# project-tsc.net
KiCad netlist of a schematic drawn in EAGLE
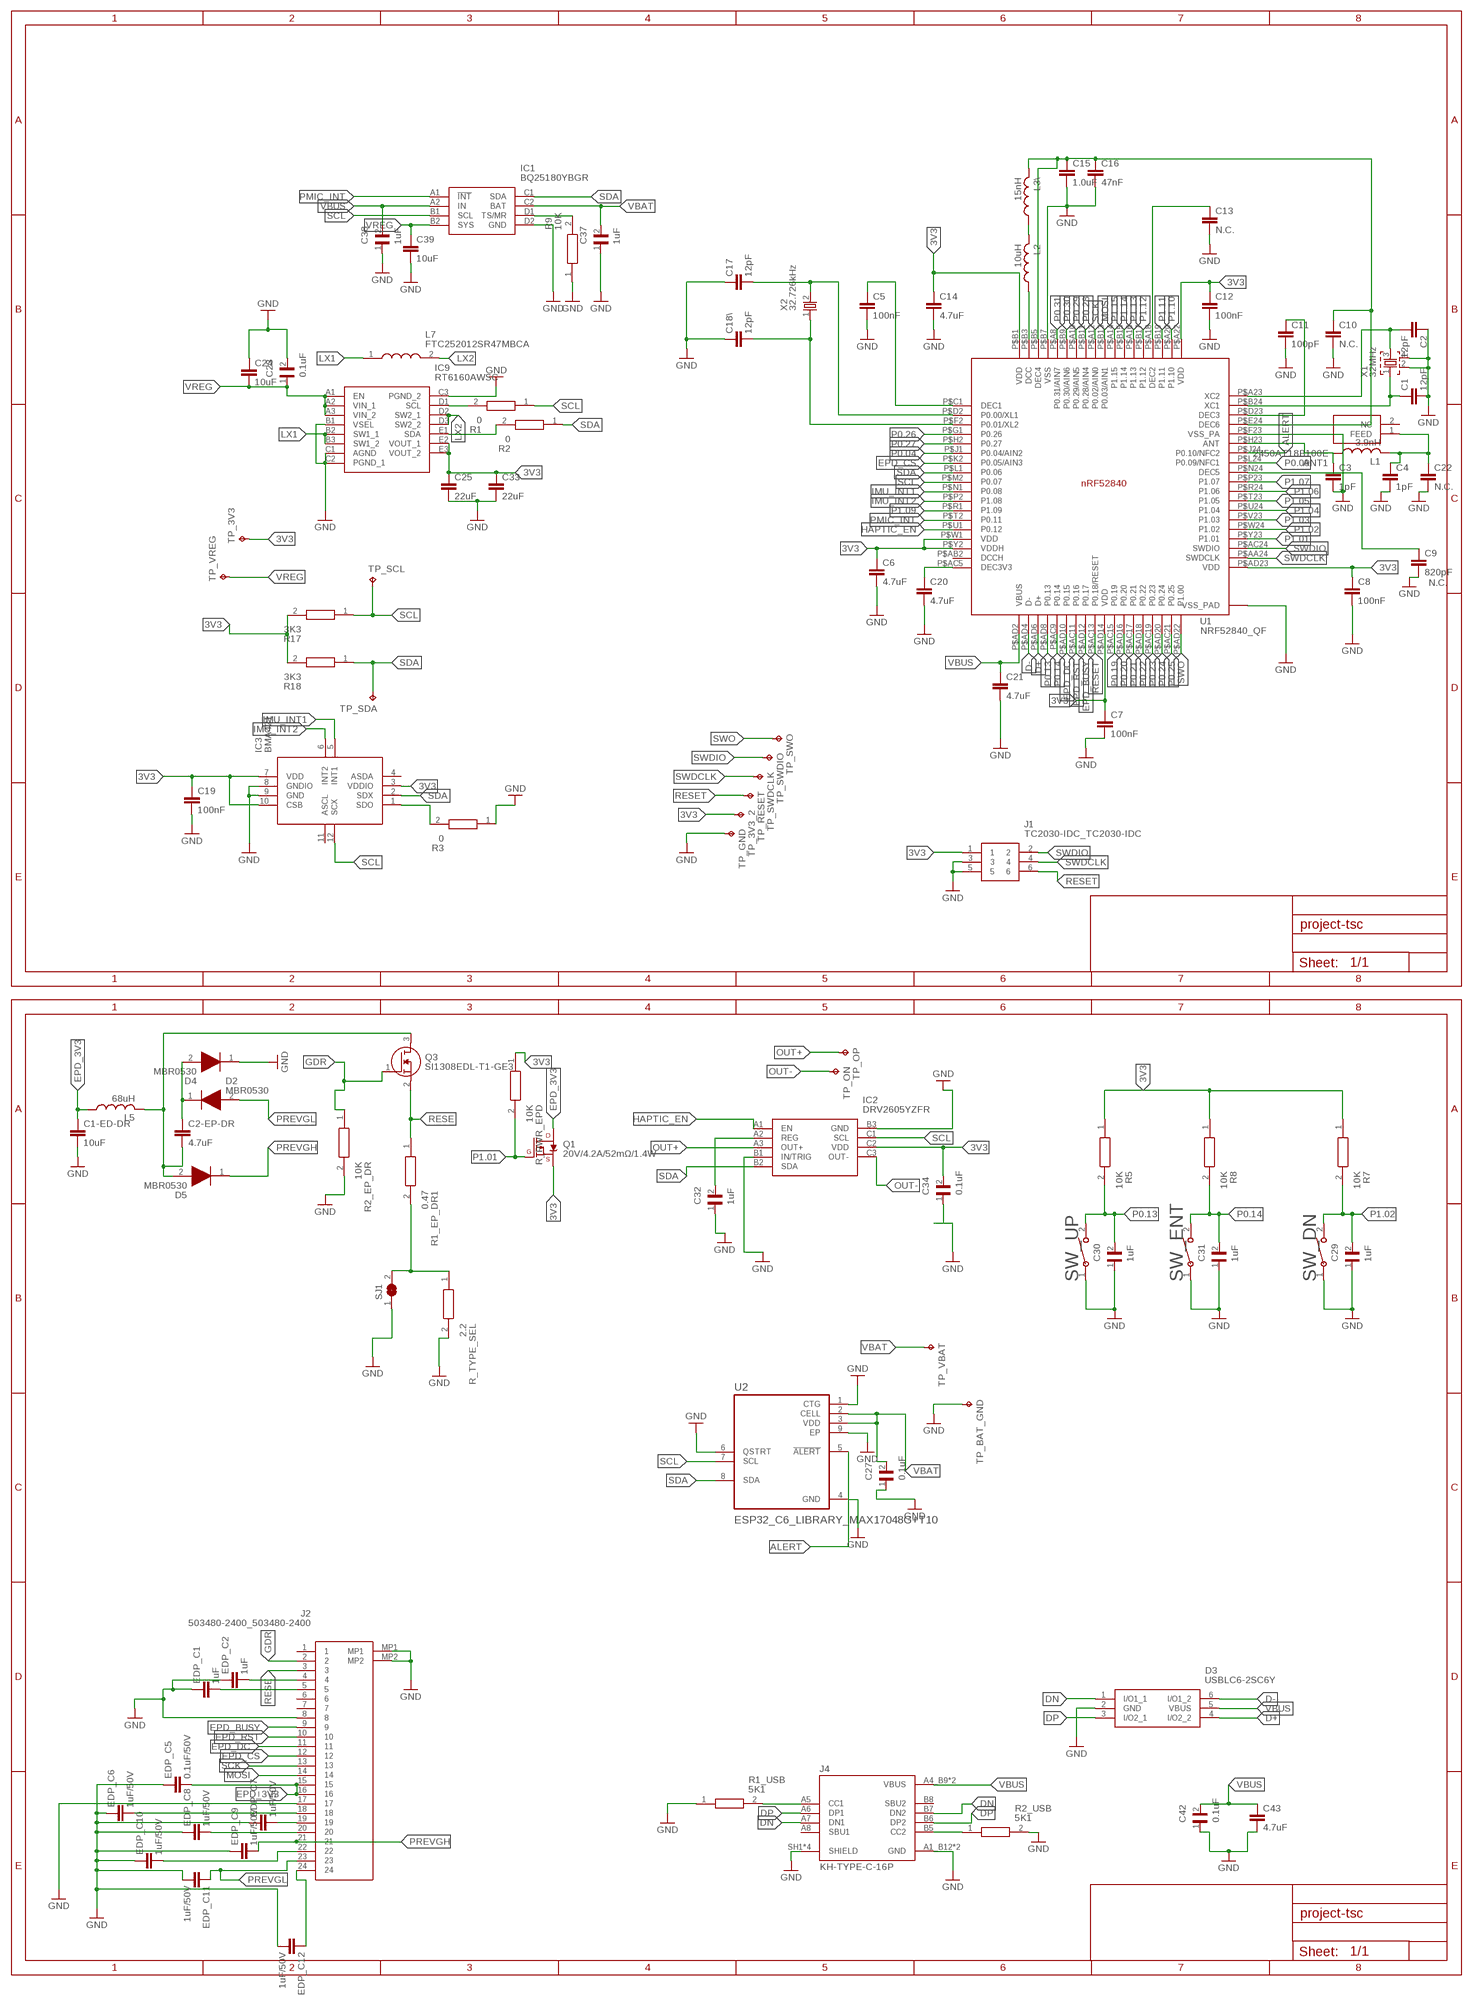
[diagram p0: schematic, sheet 1]

(export (version "E")
  (design (tool "Eeschema 10.0.6"))
  (components
    (comp (ref "ANT1")
      (value "2450AT18B100E")
      (footprint "eagle-import:2450AT18B100E_ANTC3216X140N")
      (fields (field (name "MOUSER_PART_NUMBER") "609-2450AT18B100E"))
      (libsource (lib "eagle-import") (part "2450AT18B100E_2450AT18B100E"))
    )
    (comp (ref "C1")
      (value "12pF")
      (footprint "eagle-import:NORDIC_NRF_3_RESC0201_L")
      (libsource (lib "eagle-import") (part "NORDIC_NRF_3_CAPACITOR_0201_L"))
    )
    (comp (ref "C1-ED-DR")
      (value "10uF")
      (footprint "eagle-import:NORDIC_NRF_3_RESC0402_N")
      (libsource (lib "eagle-import") (part "NORDIC_NRF_3_CAPACITOR_0402_N"))
    )
    (comp (ref "C2")
      (value "12pF")
      (footprint "eagle-import:NORDIC_NRF_3_RESC0201_L")
      (libsource (lib "eagle-import") (part "NORDIC_NRF_3_CAPACITOR_0201_L"))
    )
    (comp (ref "C2-EP-DR")
      (value "4.7uF")
      (footprint "eagle-import:NORDIC_NRF_3_RESC0402_N")
      (libsource (lib "eagle-import") (part "NORDIC_NRF_3_CAPACITOR_0402_N"))
    )
    (comp (ref "C3")
      (value "1pF")
      (footprint "eagle-import:NORDIC_NRF_3_RESC0201_N")
      (libsource (lib "eagle-import") (part "NORDIC_NRF_3_CAPACITOR_0201_N"))
    )
    (comp (ref "C4")
      (value "1pF")
      (footprint "eagle-import:NORDIC_NRF_3_RESC0201_N")
      (libsource (lib "eagle-import") (part "NORDIC_NRF_3_CAPACITOR_0201_N"))
    )
    (comp (ref "C5")
      (value "100nF")
      (footprint "eagle-import:NORDIC_NRF_3_RESC0201_L")
      (libsource (lib "eagle-import") (part "NORDIC_NRF_3_CAPACITOR_0201_L"))
    )
    (comp (ref "C6")
      (value "4.7uF")
      (footprint "eagle-import:NORDIC_NRF_3_RESC0402_N")
      (libsource (lib "eagle-import") (part "NORDIC_NRF_3_CAPACITOR_0402_N"))
    )
    (comp (ref "C7")
      (value "100nF")
      (footprint "eagle-import:NORDIC_NRF_3_RESC0201_N")
      (libsource (lib "eagle-import") (part "NORDIC_NRF_3_CAPACITOR_0201_N"))
    )
    (comp (ref "C8")
      (value "100nF")
      (footprint "eagle-import:NORDIC_NRF_3_RESC0201_N")
      (libsource (lib "eagle-import") (part "NORDIC_NRF_3_CAPACITOR_0201_N"))
    )
    (comp (ref "C9")
      (value "820pF")
      (footprint "eagle-import:NORDIC_NRF_3_RESC0201_N")
      (libsource (lib "eagle-import") (part "NORDIC_NRF_3_CAPACITOR_0201_N"))
    )
    (comp (ref "C10")
      (value "N.C.")
      (footprint "eagle-import:NORDIC_NRF_3_RESC0201_L")
      (libsource (lib "eagle-import") (part "NORDIC_NRF_3_CAPACITOR_0201_L"))
    )
    (comp (ref "C11")
      (value "100pF")
      (footprint "eagle-import:NORDIC_NRF_3_RESC0201_L")
      (libsource (lib "eagle-import") (part "NORDIC_NRF_3_CAPACITOR_0201_L"))
    )
    (comp (ref "C12")
      (value "100nF")
      (footprint "eagle-import:NORDIC_NRF_3_RESC0201_L")
      (libsource (lib "eagle-import") (part "NORDIC_NRF_3_CAPACITOR_0201_L"))
    )
    (comp (ref "C13")
      (value "N.C.")
      (footprint "eagle-import:NORDIC_NRF_3_RESC0201_L")
      (libsource (lib "eagle-import") (part "NORDIC_NRF_3_CAPACITOR_0201_L"))
    )
    (comp (ref "C14")
      (value "4.7uF")
      (footprint "eagle-import:NORDIC_NRF_3_RESC0201_L")
      (libsource (lib "eagle-import") (part "NORDIC_NRF_3_CAPACITOR_0201_L"))
    )
    (comp (ref "C15")
      (value "1.0uF")
      (footprint "eagle-import:NORDIC_NRF_3_RESC0201_L")
      (libsource (lib "eagle-import") (part "NORDIC_NRF_3_CAPACITOR_0201_L"))
    )
    (comp (ref "C16")
      (value "47nF")
      (footprint "eagle-import:NORDIC_NRF_3_RESC0201_L")
      (libsource (lib "eagle-import") (part "NORDIC_NRF_3_CAPACITOR_0201_L"))
    )
    (comp (ref "C17")
      (value "12pF")
      (footprint "eagle-import:NORDIC_NRF_3_RESC0201_L")
      (libsource (lib "eagle-import") (part "NORDIC_NRF_3_CAPACITOR_0201_L"))
    )
    (comp (ref "C18\\")
      (value "12pF")
      (footprint "eagle-import:NORDIC_NRF_3_RESC0201_L")
      (libsource (lib "eagle-import") (part "NORDIC_NRF_3_CAPACITOR_0201_L"))
    )
    (comp (ref "C19")
      (value "100nF")
      (footprint "eagle-import:NORDIC_NRF_3_RESC0201_L")
      (libsource (lib "eagle-import") (part "NORDIC_NRF_3_CAPACITOR_0201_L"))
    )
    (comp (ref "C20")
      (value "4.7uF")
      (footprint "eagle-import:NORDIC_NRF_3_RESC0402_N")
      (libsource (lib "eagle-import") (part "NORDIC_NRF_3_CAPACITOR_0402_N"))
    )
    (comp (ref "C21")
      (value "4.7uF")
      (footprint "eagle-import:NORDIC_NRF_3_RESC0402_N")
      (libsource (lib "eagle-import") (part "NORDIC_NRF_3_CAPACITOR_0402_N"))
    )
    (comp (ref "C22")
      (value "N.C.")
      (footprint "eagle-import:NORDIC_NRF_3_RESC0201_N")
      (libsource (lib "eagle-import") (part "NORDIC_NRF_3_CAPACITOR_0201_N"))
    )
    (comp (ref "C23")
      (value "0.1uF")
      (footprint "eagle-import:GRM011R60J152KE01L_2_CAPC0201X13N")
      (fields (field (name "MF") "Murata") (field (name "MP") "GRM011R60J152KE01L"))
      (libsource (lib "eagle-import") (part "GRM011R60J152KE01L_2_GRM011R60J152KE01L"))
    )
    (comp (ref "C24")
      (value "10uF")
      (footprint "eagle-import:NORDIC_NRF_3_RESC0201_L")
      (libsource (lib "eagle-import") (part "NORDIC_NRF_3_CAPACITOR_0201_L"))
    )
    (comp (ref "C25")
      (value "22uF")
      (footprint "eagle-import:NORDIC_NRF_3_RESC0201_L")
      (libsource (lib "eagle-import") (part "NORDIC_NRF_3_CAPACITOR_0201_L"))
    )
    (comp (ref "C27")
      (value "0.1uF")
      (footprint "eagle-import:GRM011R60J152KE01L_2_CAPC0201X13N")
      (fields (field (name "MF") "Murata") (field (name "MP") "GRM011R60J152KE01L"))
      (libsource (lib "eagle-import") (part "GRM011R60J152KE01L_2_GRM011R60J152KE01L"))
    )
    (comp (ref "C29")
      (value "1uF")
      (footprint "eagle-import:GRM011R60J152KE01L_2_CAPC0201X13N")
      (fields (field (name "MF") "Murata") (field (name "MP") "GRM011R60J152KE01L"))
      (libsource (lib "eagle-import") (part "GRM011R60J152KE01L_2_GRM011R60J152KE01L"))
    )
    (comp (ref "C30")
      (value "1uF")
      (footprint "eagle-import:GRM011R60J152KE01L_2_CAPC0201X13N")
      (fields (field (name "MF") "Murata") (field (name "MP") "GRM011R60J152KE01L"))
      (libsource (lib "eagle-import") (part "GRM011R60J152KE01L_2_GRM011R60J152KE01L"))
    )
    (comp (ref "C31")
      (value "1uF")
      (footprint "eagle-import:GRM011R60J152KE01L_2_CAPC0201X13N")
      (fields (field (name "MF") "Murata") (field (name "MP") "GRM011R60J152KE01L"))
      (libsource (lib "eagle-import") (part "GRM011R60J152KE01L_2_GRM011R60J152KE01L"))
    )
    (comp (ref "C32")
      (value "1uF")
      (footprint "eagle-import:GRM011R60J152KE01L_2_CAPC0201X13N")
      (fields (field (name "MF") "Murata") (field (name "MP") "GRM011R60J152KE01L"))
      (libsource (lib "eagle-import") (part "GRM011R60J152KE01L_2_GRM011R60J152KE01L"))
    )
    (comp (ref "C33")
      (value "22uF")
      (footprint "eagle-import:NORDIC_NRF_3_RESC0201_L")
      (libsource (lib "eagle-import") (part "NORDIC_NRF_3_CAPACITOR_0201_L"))
    )
    (comp (ref "C34")
      (value "0.1uF")
      (footprint "eagle-import:GRM011R60J152KE01L_2_CAPC0201X13N")
      (fields (field (name "MF") "Murata") (field (name "MP") "GRM011R60J152KE01L"))
      (libsource (lib "eagle-import") (part "GRM011R60J152KE01L_2_GRM011R60J152KE01L"))
    )
    (comp (ref "C37")
      (value "1uF")
      (footprint "eagle-import:GRM011R60J152KE01L_2_CAPC0201X13N")
      (fields (field (name "MF") "Murata") (field (name "MP") "GRM011R60J152KE01L"))
      (libsource (lib "eagle-import") (part "GRM011R60J152KE01L_2_GRM011R60J152KE01L"))
    )
    (comp (ref "C38")
      (value "1uF")
      (footprint "eagle-import:GRM011R60J152KE01L_2_CAPC0201X13N")
      (fields (field (name "MF") "Murata") (field (name "MP") "GRM011R60J152KE01L"))
      (libsource (lib "eagle-import") (part "GRM011R60J152KE01L_2_GRM011R60J152KE01L"))
    )
    (comp (ref "C39")
      (value "10uF")
      (footprint "eagle-import:NORDIC_NRF_3_RESC0201_L")
      (libsource (lib "eagle-import") (part "NORDIC_NRF_3_CAPACITOR_0201_L"))
    )
    (comp (ref "C42")
      (value "0.1uF")
      (footprint "eagle-import:GRM011R60J152KE01L_2_CAPC0201X13N")
      (fields (field (name "MF") "Murata") (field (name "MP") "GRM011R60J152KE01L"))
      (libsource (lib "eagle-import") (part "GRM011R60J152KE01L_2_GRM011R60J152KE01L"))
    )
    (comp (ref "C43")
      (value "4.7uF")
      (footprint "eagle-import:NORDIC_NRF_3_RESC0201_L")
      (libsource (lib "eagle-import") (part "NORDIC_NRF_3_CAPACITOR_0201_L"))
    )
    (comp (ref "D2")
      (value "MBR0530")
      (footprint "eagle-import:ESP32_C6_LIBRARY_5_SOD3716X135N")
      (fields (field (name "MF") "ON Semiconductor"))
      (libsource (lib "eagle-import") (part "ESP32_C6_LIBRARY_5_MBR0530"))
    )
    (comp (ref "D3")
      (value "USBLC6-2SC6Y")
      (footprint "eagle-import:ESP32_C6_LIBRARY_3_SOT95P280X145-6N")
      (fields (field (name "MF") "STMicroelectronics"))
      (libsource (lib "eagle-import") (part "ESP32_C6_LIBRARY_3_USBLC6-2SC6Y"))
    )
    (comp (ref "D4")
      (value "MBR0530")
      (footprint "eagle-import:ESP32_C6_LIBRARY_5_SOD3716X135N")
      (fields (field (name "MF") "ON Semiconductor"))
      (libsource (lib "eagle-import") (part "ESP32_C6_LIBRARY_5_MBR0530"))
    )
    (comp (ref "D5")
      (value "MBR0530")
      (footprint "eagle-import:ESP32_C6_LIBRARY_5_SOD3716X135N")
      (fields (field (name "MF") "ON Semiconductor"))
      (libsource (lib "eagle-import") (part "ESP32_C6_LIBRARY_5_MBR0530"))
    )
    (comp (ref "EDP_C1")
      (value "1uF")
      (footprint "eagle-import:NORDIC_NRF_3_RESC0201_L")
      (libsource (lib "eagle-import") (part "NORDIC_NRF_3_CAPACITOR_0201_L"))
    )
    (comp (ref "EDP_C2")
      (value "1uF")
      (footprint "eagle-import:NORDIC_NRF_3_RESC0201_L")
      (libsource (lib "eagle-import") (part "NORDIC_NRF_3_CAPACITOR_0201_L"))
    )
    (comp (ref "EDP_C5")
      (value "0.1uF/50V")
      (footprint "eagle-import:NORDIC_NRF_3_RESC0201_L")
      (libsource (lib "eagle-import") (part "NORDIC_NRF_3_CAPACITOR_0201_L"))
    )
    (comp (ref "EDP_C6")
      (value "1uF/50V")
      (footprint "eagle-import:NORDIC_NRF_3_RESC0201_L")
      (libsource (lib "eagle-import") (part "NORDIC_NRF_3_CAPACITOR_0201_L"))
    )
    (comp (ref "EDP_C7")
      (value "1uF/50V")
      (footprint "eagle-import:NORDIC_NRF_3_RESC0201_L")
      (libsource (lib "eagle-import") (part "NORDIC_NRF_3_CAPACITOR_0201_L"))
    )
    (comp (ref "EDP_C8")
      (value "1uF/50V")
      (footprint "eagle-import:NORDIC_NRF_3_RESC0201_L")
      (libsource (lib "eagle-import") (part "NORDIC_NRF_3_CAPACITOR_0201_L"))
    )
    (comp (ref "EDP_C9")
      (value "1uF/50V")
      (footprint "eagle-import:NORDIC_NRF_3_RESC0201_L")
      (libsource (lib "eagle-import") (part "NORDIC_NRF_3_CAPACITOR_0201_L"))
    )
    (comp (ref "EDP_C10")
      (value "1uF/50V")
      (footprint "eagle-import:NORDIC_NRF_3_RESC0201_L")
      (libsource (lib "eagle-import") (part "NORDIC_NRF_3_CAPACITOR_0201_L"))
    )
    (comp (ref "EDP_C11")
      (value "1uF/50V")
      (footprint "eagle-import:NORDIC_NRF_3_RESC0201_L")
      (libsource (lib "eagle-import") (part "NORDIC_NRF_3_CAPACITOR_0201_L"))
    )
    (comp (ref "EDP_C12")
      (value "1uF/50V")
      (footprint "eagle-import:NORDIC_NRF_3_RESC0201_L")
      (libsource (lib "eagle-import") (part "NORDIC_NRF_3_CAPACITOR_0201_L"))
    )
    (comp (ref "IC1")
      (value "BQ25180YBGR")
      (footprint "eagle-import:BQ25180YBGR_BGA8C40P2X4_100X155X50")
      (fields (field (name "MOUSER_PART_NUMBER") "595-BQ25180YBGR"))
      (libsource (lib "eagle-import") (part "BQ25180YBGR_BQ25180YBGR"))
    )
    (comp (ref "IC2")
      (value "DRV2605YZFR")
      (footprint "eagle-import:DRV2605YZFR_BGA9C50P3X3_144X144X62")
      (libsource (lib "eagle-import") (part "DRV2605YZFR_DRV2605YZFR"))
    )
    (comp (ref "IC3")
      (value "BMA421")
      (footprint "eagle-import:BMA423_BMA423")
      (fields (field (name "ARROW_PART_NUMBER") "BMA423") (field (name "MOUSER_PART_NUMBER") "262-BMA423"))
      (libsource (lib "eagle-import") (part "BMA423_BMA423"))
    )
    (comp (ref "IC9")
      (value "RT6160AWSC")
      (footprint "eagle-import:RT6160AWSC_BGA15C40P3X5_140X230X60")
      (fields (field (name "MOUSER_PART_NUMBER") "835-RT6160AWSC"))
      (libsource (lib "eagle-import") (part "RT6160AWSC_RT6160AWSC"))
    )
    (comp (ref "J1")
      (value "TC2030-IDC_TC2030-IDC")
      (footprint "eagle-import:TC2030-IDC_TC2030IDC")
      (fields (field (name "MANUFACTURER_PART_NUMBER") "TC2030-IDC"))
      (libsource (lib "eagle-import") (part "TC2030-IDC_TC2030-IDC"))
    )
    (comp (ref "J2")
      (value "503480-2400_503480-2400")
      (footprint "eagle-import:503480-2400_5034802400")
      (fields
        (field (name "MANUFACTURER_PART_NUMBER") "503480-2400")
        (field (name "MOUSER_PART_NUMBER") "538-503480-2400")
      )
      (libsource (lib "eagle-import") (part "503480-2400_503480-2400"))
    )
    (comp (ref "J4")
      (value "KH-TYPE-C-16P")
      (footprint "eagle-import:KH-TYPE-C-16P_KINGHELM_KH-TYPE-C-16P")
      (fields (field (name "MF") "kinghelm"))
      (libsource (lib "eagle-import") (part "KH-TYPE-C-16P_KH-TYPE-C-16P"))
    )
    (comp (ref "L1")
      (value "3.9nH")
      (footprint "eagle-import:NORDIC_NRF_2_RESC0402_L")
      (libsource (lib "eagle-import") (part "NORDIC_NRF_2_INDUCTOR_0402_L"))
    )
    (comp (ref "L2")
      (value "10uH")
      (footprint "eagle-import:NORDIC_NRF_2_RESC0402_L")
      (libsource (lib "eagle-import") (part "NORDIC_NRF_2_INDUCTOR_0402_L"))
    )
    (comp (ref "L3\\")
      (value "15nH")
      (footprint "eagle-import:NORDIC_NRF_2_RESC0402_L")
      (libsource (lib "eagle-import") (part "NORDIC_NRF_2_INDUCTOR_0402_L"))
    )
    (comp (ref "L5")
      (value "68uH")
      (footprint "eagle-import:NORDIC_NRF_2_RESC0402_L")
      (libsource (lib "eagle-import") (part "NORDIC_NRF_2_INDUCTOR_0402_L"))
    )
    (comp (ref "L7")
      (value "FTC252012SR47MBCA")
      (footprint "eagle-import:MLP2016SR47MT0S1_INDC2016X100N")
      (libsource (lib "eagle-import") (part "MLP2016SR47MT0S1_FTC252012SR47MBCA"))
    )
    (comp (ref "Q1")
      (value "20V/4.2A/52mΩ/1.4W")
      (footprint "eagle-import:ESP32_C6_LIBRARY_4_ESP32_C6_LIBRARY_4_ESP32_C6_LIBRARY_4_ESP32_C6_LIBRARY_4_ESP32_WROVER_SPARKFUN-DISCRETESEMI_SOT23-3")
      (libsource (lib "eagle-import") (part "ESP32_C6_LIBRARY_4_ESP32_WROVER_SPARKFUN-DISCRETESEMI_MOSFET_PCH-DMG2305UX-7"))
    )
    (comp (ref "Q3")
      (value "SI1308EDL-T1-GE3")
      (footprint "eagle-import:ESP32_C6_LIBRARY_6_SOT65P210X110-3N")
      (fields (field (name "MF") "Vishay Siliconix"))
      (libsource (lib "eagle-import") (part "ESP32_C6_LIBRARY_6_SI1308EDL-T1-GE3"))
    )
    (comp (ref "R1")
      (value "0")
      (footprint "eagle-import:CPF0201D7K68C1_0201")
      (libsource (lib "eagle-import") (part "CPF0201D7K68C1_CPF0201D7K68C1"))
    )
    (comp (ref "R1_EP_DR1")
      (value "0.47")
      (footprint "eagle-import:CPF0201D7K68C1_0201")
      (libsource (lib "eagle-import") (part "CPF0201D7K68C1_CPF0201D7K68C1"))
    )
    (comp (ref "R1_USB")
      (value "5K1")
      (footprint "eagle-import:CPF0201D7K68C1_0201")
      (libsource (lib "eagle-import") (part "CPF0201D7K68C1_CPF0201D7K68C1"))
    )
    (comp (ref "R2")
      (value "0")
      (footprint "eagle-import:CPF0201D7K68C1_0201")
      (libsource (lib "eagle-import") (part "CPF0201D7K68C1_CPF0201D7K68C1"))
    )
    (comp (ref "R2_EP_DR")
      (value "10K")
      (footprint "eagle-import:CPF0201D7K68C1_0201")
      (libsource (lib "eagle-import") (part "CPF0201D7K68C1_CPF0201D7K68C1"))
    )
    (comp (ref "R2_USB")
      (value "5K1")
      (footprint "eagle-import:CPF0201D7K68C1_0201")
      (libsource (lib "eagle-import") (part "CPF0201D7K68C1_CPF0201D7K68C1"))
    )
    (comp (ref "R3")
      (value "0")
      (footprint "eagle-import:CPF0201D7K68C1_0201")
      (libsource (lib "eagle-import") (part "CPF0201D7K68C1_CPF0201D7K68C1"))
    )
    (comp (ref "R5")
      (value "10K")
      (footprint "eagle-import:CPF0201D7K68C1_0201")
      (libsource (lib "eagle-import") (part "CPF0201D7K68C1_CPF0201D7K68C1"))
    )
    (comp (ref "R7")
      (value "10K")
      (footprint "eagle-import:CPF0201D7K68C1_0201")
      (libsource (lib "eagle-import") (part "CPF0201D7K68C1_CPF0201D7K68C1"))
    )
    (comp (ref "R8")
      (value "10K")
      (footprint "eagle-import:CPF0201D7K68C1_0201")
      (libsource (lib "eagle-import") (part "CPF0201D7K68C1_CPF0201D7K68C1"))
    )
    (comp (ref "R9")
      (value "10K")
      (footprint "eagle-import:CPF0201D7K68C1_0201")
      (libsource (lib "eagle-import") (part "CPF0201D7K68C1_CPF0201D7K68C1"))
    )
    (comp (ref "R17")
      (value "3K3")
      (footprint "eagle-import:CPF0201D7K68C1_0201")
      (libsource (lib "eagle-import") (part "CPF0201D7K68C1_CPF0201D7K68C1"))
    )
    (comp (ref "R18")
      (value "3K3")
      (footprint "eagle-import:CPF0201D7K68C1_0201")
      (libsource (lib "eagle-import") (part "CPF0201D7K68C1_CPF0201D7K68C1"))
    )
    (comp (ref "R_PWR_EPD")
      (value "10K")
      (footprint "eagle-import:CPF0201D7K68C1_0201")
      (libsource (lib "eagle-import") (part "CPF0201D7K68C1_CPF0201D7K68C1"))
    )
    (comp (ref "R_TYPE_SEL")
      (value "2.2")
      (footprint "eagle-import:CPF0201D7K68C1_0201")
      (libsource (lib "eagle-import") (part "CPF0201D7K68C1_CPF0201D7K68C1"))
    )
    (comp (ref "SJ1")
      (value "ESP32_C6_LIBRARY_7_JUMPER_SJ")
      (footprint "eagle-import:ESP32_C6_LIBRARY_7_JUMPER_SJ")
      (libsource (lib "eagle-import") (part "ESP32_C6_LIBRARY_7_JUMPER_SJ"))
    )
    (comp (ref "SW_DN")
      (value "2025-10-22_07-23-44_LIBRARY_EVP-AKE31ASW_EVP-AKE31A_PAN")
      (footprint "eagle-import:2025-10-22_07-23-44_LIBRARY_SW_EVP-AKE31A_PAN")
      (fields
        (field (name "MANUFACTURER_PART_NUMBER") "EVP-AKE31A")
        (field (name "COPYRIGHT") "Copyright (C) 2025 Ultra Librarian. All rights reserved.")
      )
      (libsource (lib "eagle-import") (part "2025-10-22_07-23-44_LIBRARY_EVP-AKE31ASW_EVP-AKE31A_PAN"))
    )
    (comp (ref "SW_ENT")
      (value "2025-10-22_07-23-44_LIBRARY_EVP-AKE31ASW_EVP-AKE31A_PAN")
      (footprint "eagle-import:2025-10-22_07-23-44_LIBRARY_SW_EVP-AKE31A_PAN")
      (fields
        (field (name "MANUFACTURER_PART_NUMBER") "EVP-AKE31A")
        (field (name "COPYRIGHT") "Copyright (C) 2025 Ultra Librarian. All rights reserved.")
      )
      (libsource (lib "eagle-import") (part "2025-10-22_07-23-44_LIBRARY_EVP-AKE31ASW_EVP-AKE31A_PAN"))
    )
    (comp (ref "SW_UP")
      (value "2025-10-22_07-23-44_LIBRARY_EVP-AKE31ASW_EVP-AKE31A_PAN")
      (footprint "eagle-import:2025-10-22_07-23-44_LIBRARY_SW_EVP-AKE31A_PAN")
      (fields
        (field (name "MANUFACTURER_PART_NUMBER") "EVP-AKE31A")
        (field (name "COPYRIGHT") "Copyright (C) 2025 Ultra Librarian. All rights reserved.")
      )
      (libsource (lib "eagle-import") (part "2025-10-22_07-23-44_LIBRARY_EVP-AKE31ASW_EVP-AKE31A_PAN"))
    )
    (comp (ref "TP_3V3")
      (value "HECTOR_WATCH_1_TPTP20R")
      (footprint "eagle-import:HECTOR_WATCH_1_TP20R")
      (libsource (lib "eagle-import") (part "HECTOR_WATCH_1_TPTP20R"))
    )
    (comp (ref "TP_3V3_2")
      (value "HECTOR_WATCH_1_TPTP20R")
      (footprint "eagle-import:HECTOR_WATCH_1_TP20R")
      (libsource (lib "eagle-import") (part "HECTOR_WATCH_1_TPTP20R"))
    )
    (comp (ref "TP_BAT_GND")
      (value "HECTOR_WATCH_1_TPTP20R")
      (footprint "eagle-import:HECTOR_WATCH_1_TP20R")
      (libsource (lib "eagle-import") (part "HECTOR_WATCH_1_TPTP20R"))
    )
    (comp (ref "TP_GND")
      (value "HECTOR_WATCH_1_TPTP20R")
      (footprint "eagle-import:HECTOR_WATCH_1_TP20R")
      (libsource (lib "eagle-import") (part "HECTOR_WATCH_1_TPTP20R"))
    )
    (comp (ref "TP_ON")
      (value "HECTOR_WATCH_1_TPTP20R")
      (footprint "eagle-import:HECTOR_WATCH_1_TP20R")
      (libsource (lib "eagle-import") (part "HECTOR_WATCH_1_TPTP20R"))
    )
    (comp (ref "TP_OP")
      (value "HECTOR_WATCH_1_TPTP20R")
      (footprint "eagle-import:HECTOR_WATCH_1_TP20R")
      (libsource (lib "eagle-import") (part "HECTOR_WATCH_1_TPTP20R"))
    )
    (comp (ref "TP_RESET")
      (value "HECTOR_WATCH_1_TPTP20R")
      (footprint "eagle-import:HECTOR_WATCH_1_TP20R")
      (libsource (lib "eagle-import") (part "HECTOR_WATCH_1_TPTP20R"))
    )
    (comp (ref "TP_SCL")
      (value "HECTOR_WATCH_1_TPTP20R")
      (footprint "eagle-import:HECTOR_WATCH_1_TP20R")
      (libsource (lib "eagle-import") (part "HECTOR_WATCH_1_TPTP20R"))
    )
    (comp (ref "TP_SDA")
      (value "HECTOR_WATCH_1_TPTP20R")
      (footprint "eagle-import:HECTOR_WATCH_1_TP20R")
      (libsource (lib "eagle-import") (part "HECTOR_WATCH_1_TPTP20R"))
    )
    (comp (ref "TP_SWDCLK")
      (value "HECTOR_WATCH_1_TPTP20R")
      (footprint "eagle-import:HECTOR_WATCH_1_TP20R")
      (libsource (lib "eagle-import") (part "HECTOR_WATCH_1_TPTP20R"))
    )
    (comp (ref "TP_SWDIO")
      (value "HECTOR_WATCH_1_TPTP20R")
      (footprint "eagle-import:HECTOR_WATCH_1_TP20R")
      (libsource (lib "eagle-import") (part "HECTOR_WATCH_1_TPTP20R"))
    )
    (comp (ref "TP_SWO")
      (value "HECTOR_WATCH_1_TPTP20R")
      (footprint "eagle-import:HECTOR_WATCH_1_TP20R")
      (libsource (lib "eagle-import") (part "HECTOR_WATCH_1_TPTP20R"))
    )
    (comp (ref "TP_VBAT")
      (value "HECTOR_WATCH_1_TPTP20R")
      (footprint "eagle-import:HECTOR_WATCH_1_TP20R")
      (libsource (lib "eagle-import") (part "HECTOR_WATCH_1_TPTP20R"))
    )
    (comp (ref "TP_VREG")
      (value "HECTOR_WATCH_1_TPTP20R")
      (footprint "eagle-import:HECTOR_WATCH_1_TP20R")
      (libsource (lib "eagle-import") (part "HECTOR_WATCH_1_TPTP20R"))
    )
    (comp (ref "U1")
      (value "NRF52840_QF")
      (footprint "eagle-import:NORDIC_NRF_4_AQFN50P700X700X85_HS-74N")
      (libsource (lib "eagle-import") (part "NORDIC_NRF_4_NRF52840_QF"))
    )
    (comp (ref "U2")
      (value "ESP32_C6_LIBRARY_MAX17048G+T10")
      (footprint "eagle-import:ESP32_C6_LIBRARY_SON50P200X200X80-9N")
      (fields (field (name "MF") "Analog Devices") (field (name "MP") "MAX17048G+T10"))
      (libsource (lib "eagle-import") (part "ESP32_C6_LIBRARY_MAX17048G+T10"))
    )
    (comp (ref "X1")
      (value "32MHz")
      (footprint "eagle-import:NORDIC_NRF_BT-XTAL_2016_N")
      (libsource (lib "eagle-import") (part "NORDIC_NRF_XTAL_32MHZ"))
    )
    (comp (ref "X2")
      (value "32.726kHz")
      (footprint "eagle-import:NORDIC_NRF_1_XTAL_3215_N")
      (libsource (lib "eagle-import") (part "NORDIC_NRF_1_XTAL_32KHZ"))
    )
  )
  (nets
    (net (code "1") (name "3V3") (class "Default")
      (node (ref "C12") (pin "1") (pinfunction "1_1") (pintype "passive"))
      (node (ref "C14") (pin "1") (pinfunction "1_1") (pintype "passive"))
      (node (ref "C19") (pin "1") (pinfunction "1_1") (pintype "passive"))
      (node (ref "C25") (pin "1") (pinfunction "1_1") (pintype "passive"))
      (node (ref "C33") (pin "1") (pinfunction "1_1") (pintype "passive"))
      (node (ref "C34") (pin "2") (pinfunction "2_2") (pintype "passive"))
      (node (ref "C6") (pin "1") (pinfunction "1_1") (pintype "passive"))
      (node (ref "C7") (pin "1") (pinfunction "1_1") (pintype "passive"))
      (node (ref "C8") (pin "1") (pinfunction "1_1") (pintype "passive"))
      (node (ref "IC2") (pin "C2") (pinfunction "VDD_C2") (pintype "bidirectional"))
      (node (ref "IC3") (pin "10") (pinfunction "CSB_10") (pintype "bidirectional"))
      (node (ref "IC3") (pin "3") (pinfunction "VDDIO_3") (pintype "bidirectional"))
      (node (ref "IC3") (pin "7") (pinfunction "VDD_7") (pintype "bidirectional"))
      (node (ref "IC9") (pin "E2") (pinfunction "VOUT_1_E2") (pintype "bidirectional"))
      (node (ref "IC9") (pin "E3") (pinfunction "VOUT_2_E3") (pintype "bidirectional"))
      (node (ref "J1") (pin "1") (pinfunction "1_1") (pintype "bidirectional"))
      (node (ref "Q1") (pin "2") (pinfunction "S_2") (pintype "bidirectional"))
      (node (ref "R17") (pin "2") (pinfunction "2_2") (pintype "bidirectional"))
      (node (ref "R18") (pin "2") (pinfunction "2_2") (pintype "bidirectional"))
      (node (ref "R5") (pin "1") (pinfunction "1_1") (pintype "bidirectional"))
      (node (ref "R7") (pin "1") (pinfunction "1_1") (pintype "bidirectional"))
      (node (ref "R8") (pin "1") (pinfunction "1_1") (pintype "bidirectional"))
      (node (ref "R_PWR_EPD") (pin "1") (pinfunction "1_1") (pintype "bidirectional"))
      (node (ref "TP_3V3") (pin "TP") (pinfunction "TP_TP") (pintype "input"))
      (node (ref "TP_3V3_2") (pin "TP") (pinfunction "TP_TP") (pintype "input"))
      (node (ref "U1") (pin "P$A22") (pinfunction "VDD_P$A22") (pintype "power_in"))
      (node (ref "U1") (pin "P$AD14") (pinfunction "VDD_P$AD14") (pintype "power_in"))
      (node (ref "U1") (pin "P$AD23") (pinfunction "VDD_P$AD23") (pintype "power_in"))
      (node (ref "U1") (pin "P$B1") (pinfunction "VDD_P$B1") (pintype "power_in"))
      (node (ref "U1") (pin "P$W1") (pinfunction "VDD_P$W1") (pintype "power_in"))
      (node (ref "U1") (pin "P$Y2") (pinfunction "VDDH_P$Y2") (pintype "power_in"))
    )
    (net (code "2") (name "ALERT") (class "Default")
      (node (ref "U1") (pin "P$J24") (pinfunction "P0.10/NFC2_P$J24") (pintype "bidirectional"))
      (node (ref "U2") (pin "5") (pinfunction "~{ALERT}_5") (pintype "output"))
    )
    (net (code "3") (name "D+") (class "Default")
      (node (ref "D3") (pin "4") (pinfunction "I/O2_2_4") (pintype "bidirectional"))
      (node (ref "U1") (pin "P$AD6") (pinfunction "D+_P$AD6") (pintype "bidirectional"))
    )
    (net (code "4") (name "D-") (class "Default")
      (node (ref "D3") (pin "6") (pinfunction "I/O1_2_6") (pintype "bidirectional"))
      (node (ref "U1") (pin "P$AD4") (pinfunction "D-_P$AD4") (pintype "bidirectional"))
    )
    (net (code "5") (name "DN") (class "Default")
      (node (ref "D3") (pin "1") (pinfunction "I/O1_1_1") (pintype "bidirectional"))
      (node (ref "J4") (pin "A7") (pinfunction "DN1_A7") (pintype "bidirectional"))
      (node (ref "J4") (pin "B7") (pinfunction "DN2_B7") (pintype "bidirectional"))
    )
    (net (code "6") (name "DP") (class "Default")
      (node (ref "D3") (pin "3") (pinfunction "I/O2_1_3") (pintype "bidirectional"))
      (node (ref "J4") (pin "A6") (pinfunction "DP1_A6") (pintype "bidirectional"))
      (node (ref "J4") (pin "B6") (pinfunction "DP2_B6") (pintype "bidirectional"))
    )
    (net (code "7") (name "EPD_3V3") (class "Default")
      (node (ref "C1-ED-DR") (pin "1") (pinfunction "1_1") (pintype "passive"))
      (node (ref "EDP_C5") (pin "2") (pinfunction "2_2") (pintype "passive"))
      (node (ref "J2") (pin "15") (pinfunction "15_15") (pintype "bidirectional"))
      (node (ref "J2") (pin "16") (pinfunction "16_16") (pintype "bidirectional"))
      (node (ref "L5") (pin "1") (pinfunction "1_1") (pintype "passive"))
      (node (ref "Q1") (pin "3") (pinfunction "D_3") (pintype "bidirectional"))
    )
    (net (code "8") (name "EPD_BUSY") (class "Default")
      (node (ref "J2") (pin "9") (pinfunction "9_9") (pintype "bidirectional"))
      (node (ref "U1") (pin "P$AD12") (pinfunction "P0.17_P$AD12") (pintype "bidirectional"))
    )
    (net (code "9") (name "EPD_CS") (class "Default")
      (node (ref "J2") (pin "12") (pinfunction "12_12") (pintype "bidirectional"))
      (node (ref "U1") (pin "P$K2") (pinfunction "P0.05/AIN3_P$K2") (pintype "bidirectional"))
    )
    (net (code "10") (name "EPD_DC") (class "Default")
      (node (ref "J2") (pin "11") (pinfunction "11_11") (pintype "bidirectional"))
      (node (ref "U1") (pin "P$AD10") (pinfunction "P0.15_P$AD10") (pintype "bidirectional"))
    )
    (net (code "11") (name "EPD_RST") (class "Default")
      (node (ref "J2") (pin "10") (pinfunction "10_10") (pintype "bidirectional"))
      (node (ref "U1") (pin "P$AC11") (pinfunction "P0.16_P$AC11") (pintype "bidirectional"))
    )
    (net (code "12") (name "GDR") (class "Default")
      (node (ref "J2") (pin "2") (pinfunction "2_2") (pintype "bidirectional"))
      (node (ref "Q3") (pin "1") (pinfunction "G_1") (pintype "bidirectional"))
      (node (ref "R2_EP_DR") (pin "1") (pinfunction "1_1") (pintype "bidirectional"))
    )
    (net (code "13") (name "GND") (class "Default")
      (node (ref "C1") (pin "2") (pinfunction "2_2") (pintype "passive"))
      (node (ref "C1-ED-DR") (pin "2") (pinfunction "2_2") (pintype "passive"))
      (node (ref "C10") (pin "2") (pinfunction "2_2") (pintype "passive"))
      (node (ref "C11") (pin "2") (pinfunction "2_2") (pintype "passive"))
      (node (ref "C12") (pin "2") (pinfunction "2_2") (pintype "passive"))
      (node (ref "C13") (pin "2") (pinfunction "2_2") (pintype "passive"))
      (node (ref "C14") (pin "2") (pinfunction "2_2") (pintype "passive"))
      (node (ref "C15") (pin "2") (pinfunction "2_2") (pintype "passive"))
      (node (ref "C16") (pin "2") (pinfunction "2_2") (pintype "passive"))
      (node (ref "C17") (pin "1") (pinfunction "1_1") (pintype "passive"))
      (node (ref "C18\\") (pin "1") (pinfunction "1_1") (pintype "passive"))
      (node (ref "C19") (pin "2") (pinfunction "2_2") (pintype "passive"))
      (node (ref "C2") (pin "1") (pinfunction "1_1") (pintype "passive"))
      (node (ref "C20") (pin "2") (pinfunction "2_2") (pintype "passive"))
      (node (ref "C21") (pin "2") (pinfunction "2_2") (pintype "passive"))
      (node (ref "C22") (pin "2") (pinfunction "2_2") (pintype "passive"))
      (node (ref "C23") (pin "2") (pinfunction "2_2") (pintype "passive"))
      (node (ref "C24") (pin "1") (pinfunction "1_1") (pintype "passive"))
      (node (ref "C25") (pin "2") (pinfunction "2_2") (pintype "passive"))
      (node (ref "C27") (pin "1") (pinfunction "1_1") (pintype "passive"))
      (node (ref "C29") (pin "1") (pinfunction "1_1") (pintype "passive"))
      (node (ref "C3") (pin "2") (pinfunction "2_2") (pintype "passive"))
      (node (ref "C30") (pin "1") (pinfunction "1_1") (pintype "passive"))
      (node (ref "C31") (pin "1") (pinfunction "1_1") (pintype "passive"))
      (node (ref "C32") (pin "1") (pinfunction "1_1") (pintype "passive"))
      (node (ref "C33") (pin "2") (pinfunction "2_2") (pintype "passive"))
      (node (ref "C34") (pin "1") (pinfunction "1_1") (pintype "passive"))
      (node (ref "C37") (pin "1") (pinfunction "1_1") (pintype "passive"))
      (node (ref "C38") (pin "1") (pinfunction "1_1") (pintype "passive"))
      (node (ref "C39") (pin "2") (pinfunction "2_2") (pintype "passive"))
      (node (ref "C4") (pin "2") (pinfunction "2_2") (pintype "passive"))
      (node (ref "C42") (pin "1") (pinfunction "1_1") (pintype "passive"))
      (node (ref "C43") (pin "2") (pinfunction "2_2") (pintype "passive"))
      (node (ref "C5") (pin "2") (pinfunction "2_2") (pintype "passive"))
      (node (ref "C6") (pin "2") (pinfunction "2_2") (pintype "passive"))
      (node (ref "C7") (pin "2") (pinfunction "2_2") (pintype "passive"))
      (node (ref "C8") (pin "2") (pinfunction "2_2") (pintype "passive"))
      (node (ref "C9") (pin "2") (pinfunction "2_2") (pintype "passive"))
      (node (ref "D3") (pin "2") (pinfunction "GND_2") (pintype "bidirectional"))
      (node (ref "D4") (pin "1") (pinfunction "K_1") (pintype "bidirectional"))
      (node (ref "EDP_C1") (pin "1") (pinfunction "1_1") (pintype "passive"))
      (node (ref "EDP_C10") (pin "1") (pinfunction "1_1") (pintype "passive"))
      (node (ref "EDP_C11") (pin "2") (pinfunction "2_2") (pintype "passive"))
      (node (ref "EDP_C12") (pin "2") (pinfunction "2_2") (pintype "passive"))
      (node (ref "EDP_C2") (pin "1") (pinfunction "1_1") (pintype "passive"))
      (node (ref "EDP_C5") (pin "1") (pinfunction "1_1") (pintype "passive"))
      (node (ref "EDP_C6") (pin "1") (pinfunction "1_1") (pintype "passive"))
      (node (ref "EDP_C7") (pin "1") (pinfunction "1_1") (pintype "passive"))
      (node (ref "EDP_C8") (pin "1") (pinfunction "1_1") (pintype "passive"))
      (node (ref "EDP_C9") (pin "1") (pinfunction "1_1") (pintype "passive"))
      (node (ref "IC1") (pin "D2") (pinfunction "GND_D2") (pintype "bidirectional"))
      (node (ref "IC2") (pin "B1") (pinfunction "IN/TRIG_B1") (pintype "bidirectional"))
      (node (ref "IC2") (pin "B3") (pinfunction "GND_B3") (pintype "bidirectional"))
      (node (ref "IC3") (pin "8") (pinfunction "GNDIO_8") (pintype "bidirectional"))
      (node (ref "IC3") (pin "9") (pinfunction "GND_9") (pintype "bidirectional"))
      (node (ref "IC9") (pin "B1") (pinfunction "VSEL_B1") (pintype "bidirectional"))
      (node (ref "IC9") (pin "C1") (pinfunction "AGND_C1") (pintype "bidirectional"))
      (node (ref "IC9") (pin "C2") (pinfunction "PGND_1_C2") (pintype "bidirectional"))
      (node (ref "IC9") (pin "C3") (pinfunction "PGND_2_C3") (pintype "bidirectional"))
      (node (ref "J1") (pin "3") (pinfunction "3_3") (pintype "bidirectional"))
      (node (ref "J1") (pin "5") (pinfunction "5_5") (pintype "bidirectional"))
      (node (ref "J2") (pin "17") (pinfunction "17_17") (pintype "bidirectional"))
      (node (ref "J2") (pin "8") (pinfunction "8_8") (pintype "bidirectional"))
      (node (ref "J2") (pin "MP1") (pinfunction "MP1_MP1") (pintype "bidirectional"))
      (node (ref "J2") (pin "MP2") (pinfunction "MP2_MP2") (pintype "bidirectional"))
      (node (ref "J4") (pin "A12_B1") (pinfunction "GND_A12_B1") (pintype "power_in"))
      (node (ref "J4") (pin "A1_B12") (pinfunction "GND_A1_B12") (pintype "power_in"))
      (node (ref "J4") (pin "SH1") (pinfunction "SHIELD_SH1") (pintype "passive"))
      (node (ref "J4") (pin "SH2") (pinfunction "SHIELD_SH2") (pintype "passive"))
      (node (ref "J4") (pin "SH3") (pinfunction "SHIELD_SH3") (pintype "passive"))
      (node (ref "J4") (pin "SH4") (pinfunction "SHIELD_SH4") (pintype "passive"))
      (node (ref "R1_USB") (pin "1") (pinfunction "1_1") (pintype "bidirectional"))
      (node (ref "R2_EP_DR") (pin "2") (pinfunction "2_2") (pintype "bidirectional"))
      (node (ref "R2_USB") (pin "2") (pinfunction "2_2") (pintype "bidirectional"))
      (node (ref "R3") (pin "1") (pinfunction "1_1") (pintype "bidirectional"))
      (node (ref "R9") (pin "1") (pinfunction "1_1") (pintype "bidirectional"))
      (node (ref "R_TYPE_SEL") (pin "2") (pinfunction "2_2") (pintype "bidirectional"))
      (node (ref "SJ1") (pin "1") (pinfunction "1_1") (pintype "passive"))
      (node (ref "SW_DN") (pin "1") (pinfunction "1_1") (pintype "passive"))
      (node (ref "SW_ENT") (pin "1") (pinfunction "1_1") (pintype "passive"))
      (node (ref "SW_UP") (pin "1") (pinfunction "1_1") (pintype "passive"))
      (node (ref "TP_BAT_GND") (pin "TP") (pinfunction "TP_TP") (pintype "input"))
      (node (ref "TP_GND") (pin "TP") (pinfunction "TP_TP") (pintype "input"))
      (node (ref "U1") (pin "P$74") (pinfunction "VSS_PAD_P$74") (pintype "bidirectional"))
      (node (ref "U1") (pin "P$75") (pinfunction "VSS_PAD_P$75") (pintype "bidirectional"))
      (node (ref "U1") (pin "P$76") (pinfunction "VSS_PAD_P$76") (pintype "bidirectional"))
      (node (ref "U1") (pin "P$77") (pinfunction "VSS_PAD_P$77") (pintype "bidirectional"))
      (node (ref "U1") (pin "P$78") (pinfunction "VSS_PAD_P$78") (pintype "bidirectional"))
      (node (ref "U1") (pin "P$79") (pinfunction "VSS_PAD_P$79") (pintype "bidirectional"))
      (node (ref "U1") (pin "P$80") (pinfunction "VSS_PAD_P$80") (pintype "bidirectional"))
      (node (ref "U1") (pin "P$81") (pinfunction "VSS_PAD_P$81") (pintype "bidirectional"))
      (node (ref "U1") (pin "P$82") (pinfunction "VSS_PAD_P$82") (pintype "bidirectional"))
      (node (ref "U1") (pin "P$83") (pinfunction "VSS_PAD_P$83") (pintype "bidirectional"))
      (node (ref "U1") (pin "P$84") (pinfunction "VSS_PAD_P$84") (pintype "bidirectional"))
      (node (ref "U1") (pin "P$85") (pinfunction "VSS_PAD_P$85") (pintype "bidirectional"))
      (node (ref "U1") (pin "P$86") (pinfunction "VSS_PAD_P$86") (pintype "bidirectional"))
      (node (ref "U1") (pin "P$87") (pinfunction "VSS_PAD_P$87") (pintype "bidirectional"))
      (node (ref "U1") (pin "P$88") (pinfunction "VSS_PAD_P$88") (pintype "bidirectional"))
      (node (ref "U1") (pin "P$89") (pinfunction "VSS_PAD_P$89") (pintype "bidirectional"))
      (node (ref "U1") (pin "P$90") (pinfunction "VSS_PAD_P$90") (pintype "bidirectional"))
      (node (ref "U1") (pin "P$B7") (pinfunction "VSS_P$B7") (pintype "power_in"))
      (node (ref "U1") (pin "P$F23") (pinfunction "VSS_PA_P$F23") (pintype "bidirectional"))
      (node (ref "U2") (pin "1") (pinfunction "CTG_1") (pintype "power_in"))
      (node (ref "U2") (pin "4") (pinfunction "GND_4") (pintype "power_in"))
      (node (ref "U2") (pin "6") (pinfunction "QSTRT_6") (pintype "input"))
      (node (ref "U2") (pin "9") (pinfunction "EP_9") (pintype "power_in"))
      (node (ref "X1") (pin "2") (pinfunction "2_2") (pintype "passive"))
      (node (ref "X1") (pin "4") (pinfunction "4_4") (pintype "passive"))
    )
    (net (code "14") (name "HAPTIC_EN") (class "Default")
      (node (ref "IC2") (pin "A1") (pinfunction "EN_A1") (pintype "bidirectional"))
      (node (ref "U1") (pin "P$U1") (pinfunction "P0.12_P$U1") (pintype "bidirectional"))
    )
    (net (code "15") (name "IMU_INT1") (class "Default")
      (node (ref "IC3") (pin "5") (pinfunction "INT1_5") (pintype "bidirectional"))
      (node (ref "U1") (pin "P$N1") (pinfunction "P0.08_P$N1") (pintype "bidirectional"))
    )
    (net (code "16") (name "IMU_INT2") (class "Default")
      (node (ref "IC3") (pin "6") (pinfunction "INT2_6") (pintype "bidirectional"))
      (node (ref "U1") (pin "P$P2") (pinfunction "P1.08_P$P2") (pintype "bidirectional"))
    )
    (net (code "17") (name "LX1") (class "Default")
      (node (ref "IC9") (pin "B2") (pinfunction "SW1_1_B2") (pintype "bidirectional"))
      (node (ref "IC9") (pin "B3") (pinfunction "SW1_2_B3") (pintype "bidirectional"))
      (node (ref "L7") (pin "1") (pinfunction "1_1") (pintype "bidirectional"))
    )
    (net (code "18") (name "LX2") (class "Default")
      (node (ref "IC9") (pin "D2") (pinfunction "SW2_1_D2") (pintype "bidirectional"))
      (node (ref "IC9") (pin "D3") (pinfunction "SW2_2_D3") (pintype "bidirectional"))
      (node (ref "L7") (pin "2") (pinfunction "2_2") (pintype "bidirectional"))
    )
    (net (code "19") (name "MOSI") (class "Default")
      (node (ref "J2") (pin "14") (pinfunction "14_14") (pintype "bidirectional"))
      (node (ref "U1") (pin "P$B13") (pinfunction "P0.03/AIN1_P$B13") (pintype "bidirectional"))
    )
    (net (code "20") (name "Net-(ANT1-FEED)") (class "Default")
      (node (ref "ANT1") (pin "1") (pinfunction "FEED_1") (pintype "input"))
      (node (ref "C22") (pin "1") (pinfunction "1_1") (pintype "passive"))
      (node (ref "C4") (pin "1") (pinfunction "1_1") (pintype "passive"))
      (node (ref "L1") (pin "2") (pinfunction "2_2") (pintype "passive"))
    )
    (net (code "21") (name "Net-(D2-K)") (class "Default")
      (node (ref "C2-EP-DR") (pin "1") (pinfunction "1_1") (pintype "passive"))
      (node (ref "D2") (pin "1") (pinfunction "K_1") (pintype "bidirectional"))
      (node (ref "D4") (pin "2") (pinfunction "A_2") (pintype "bidirectional"))
    )
    (net (code "22") (name "Net-(D5-A)") (class "Default")
      (node (ref "C2-EP-DR") (pin "2") (pinfunction "2_2") (pintype "passive"))
      (node (ref "D5") (pin "2") (pinfunction "A_2") (pintype "bidirectional"))
      (node (ref "L5") (pin "2") (pinfunction "2_2") (pintype "passive"))
      (node (ref "Q3") (pin "3") (pinfunction "D_3") (pintype "bidirectional"))
    )
    (net (code "23") (name "Net-(EDP_C1-Pad2)") (class "Default")
      (node (ref "EDP_C1") (pin "2") (pinfunction "2_2") (pintype "passive"))
      (node (ref "J2") (pin "5") (pinfunction "5_5") (pintype "bidirectional"))
    )
    (net (code "24") (name "Net-(EDP_C2-Pad2)") (class "Default")
      (node (ref "EDP_C2") (pin "2") (pinfunction "2_2") (pintype "passive"))
      (node (ref "J2") (pin "4") (pinfunction "4_4") (pintype "bidirectional"))
    )
    (net (code "25") (name "Net-(EDP_C6-Pad2)") (class "Default")
      (node (ref "EDP_C6") (pin "2") (pinfunction "2_2") (pintype "passive"))
      (node (ref "J2") (pin "18") (pinfunction "18_18") (pintype "bidirectional"))
    )
    (net (code "26") (name "Net-(EDP_C7-Pad2)") (class "Default")
      (node (ref "EDP_C7") (pin "2") (pinfunction "2_2") (pintype "passive"))
      (node (ref "J2") (pin "19") (pinfunction "19_19") (pintype "bidirectional"))
    )
    (net (code "27") (name "Net-(EDP_C8-Pad2)") (class "Default")
      (node (ref "EDP_C8") (pin "2") (pinfunction "2_2") (pintype "passive"))
      (node (ref "J2") (pin "20") (pinfunction "20_20") (pintype "bidirectional"))
    )
    (net (code "28") (name "Net-(EDP_C10-Pad2)") (class "Default")
      (node (ref "EDP_C10") (pin "2") (pinfunction "2_2") (pintype "passive"))
      (node (ref "J2") (pin "22") (pinfunction "22_22") (pintype "bidirectional"))
    )
    (net (code "29") (name "Net-(EDP_C12-Pad1)") (class "Default")
      (node (ref "EDP_C12") (pin "1") (pinfunction "1_1") (pintype "passive"))
      (node (ref "J2") (pin "24") (pinfunction "24_24") (pintype "bidirectional"))
    )
    (net (code "30") (name "Net-(IC1-TS{slash}MR)") (class "Default")
      (node (ref "IC1") (pin "D1") (pinfunction "TS/MR_D1") (pintype "bidirectional"))
      (node (ref "R9") (pin "2") (pinfunction "2_2") (pintype "bidirectional"))
    )
    (net (code "31") (name "Net-(IC2-REG)") (class "Default")
      (node (ref "C32") (pin "2") (pinfunction "2_2") (pintype "passive"))
      (node (ref "IC2") (pin "A2") (pinfunction "REG_A2") (pintype "bidirectional"))
    )
    (net (code "32") (name "Net-(IC3-SDO)") (class "Default")
      (node (ref "IC3") (pin "1") (pinfunction "SDO_1") (pintype "bidirectional"))
      (node (ref "R3") (pin "2") (pinfunction "2_2") (pintype "bidirectional"))
    )
    (net (code "33") (name "Net-(IC9-SCL)") (class "Default")
      (node (ref "IC9") (pin "D1") (pinfunction "SCL_D1") (pintype "bidirectional"))
      (node (ref "R1") (pin "2") (pinfunction "2_2") (pintype "bidirectional"))
    )
    (net (code "34") (name "Net-(IC9-SDA)") (class "Default")
      (node (ref "IC9") (pin "E1") (pinfunction "SDA_E1") (pintype "bidirectional"))
      (node (ref "R2") (pin "2") (pinfunction "2_2") (pintype "bidirectional"))
    )
    (net (code "35") (name "Net-(J4-CC1)") (class "Default")
      (node (ref "J4") (pin "A5") (pinfunction "CC1_A5") (pintype "bidirectional"))
      (node (ref "R1_USB") (pin "2") (pinfunction "2_2") (pintype "bidirectional"))
    )
    (net (code "36") (name "Net-(J4-CC2)") (class "Default")
      (node (ref "J4") (pin "B5") (pinfunction "CC2_B5") (pintype "bidirectional"))
      (node (ref "R2_USB") (pin "1") (pinfunction "1_1") (pintype "bidirectional"))
    )
    (net (code "37") (name "Net-(L2-Pad2)") (class "Default")
      (node (ref "L2") (pin "2") (pinfunction "2_2") (pintype "passive"))
      (node (ref "L3\\") (pin "1") (pinfunction "1_1") (pintype "passive"))
    )
    (net (code "38") (name "Net-(R1_EP_DR1-Pad2)") (class "Default")
      (node (ref "R1_EP_DR1") (pin "2") (pinfunction "2_2") (pintype "bidirectional"))
      (node (ref "R_TYPE_SEL") (pin "1") (pinfunction "1_1") (pintype "bidirectional"))
      (node (ref "SJ1") (pin "2") (pinfunction "2_2") (pintype "passive"))
    )
    (net (code "39") (name "Net-(U1-ANT)") (class "Default")
      (node (ref "C3") (pin "1") (pinfunction "1_1") (pintype "passive"))
      (node (ref "L1") (pin "1") (pinfunction "1_1") (pintype "passive"))
      (node (ref "U1") (pin "P$H23") (pinfunction "ANT_P$H23") (pintype "bidirectional"))
    )
    (net (code "40") (name "Net-(U1-DCC)") (class "Default")
      (node (ref "L2") (pin "1") (pinfunction "1_1") (pintype "passive"))
      (node (ref "U1") (pin "P$B3") (pinfunction "DCC_P$B3") (pintype "output"))
    )
    (net (code "41") (name "Net-(U1-DEC1)") (class "Default")
      (node (ref "C5") (pin "1") (pinfunction "1_1") (pintype "passive"))
      (node (ref "U1") (pin "P$C1") (pinfunction "DEC1_P$C1") (pintype "power_in"))
    )
    (net (code "42") (name "Net-(U1-DEC2)") (class "Default")
      (node (ref "C13") (pin "1") (pinfunction "1_1") (pintype "passive"))
      (node (ref "U1") (pin "P$A18") (pinfunction "DEC2_P$A18") (pintype "bidirectional"))
    )
    (net (code "43") (name "Net-(U1-DEC3)") (class "Default")
      (node (ref "C11") (pin "1") (pinfunction "1_1") (pintype "passive"))
      (node (ref "U1") (pin "P$D23") (pinfunction "DEC3_P$D23") (pintype "bidirectional"))
    )
    (net (code "44") (name "Net-(U1-DEC3V3)") (class "Default")
      (node (ref "C20") (pin "1") (pinfunction "1_1") (pintype "passive"))
      (node (ref "U1") (pin "P$AC5") (pinfunction "DEC3V3_P$AC5") (pintype "bidirectional"))
    )
    (net (code "45") (name "Net-(U1-DEC4)") (class "Default")
      (node (ref "C10") (pin "1") (pinfunction "1_1") (pintype "passive"))
      (node (ref "C15") (pin "1") (pinfunction "1_1") (pintype "passive"))
      (node (ref "C16") (pin "1") (pinfunction "1_1") (pintype "passive"))
      (node (ref "L3\\") (pin "2") (pinfunction "2_2") (pintype "passive"))
      (node (ref "U1") (pin "P$B5") (pinfunction "DEC4_P$B5") (pintype "power_in"))
      (node (ref "U1") (pin "P$E24") (pinfunction "DEC6_P$E24") (pintype "bidirectional"))
    )
    (net (code "46") (name "Net-(U1-DEC5)") (class "Default")
      (node (ref "C9") (pin "1") (pinfunction "1_1") (pintype "passive"))
      (node (ref "U1") (pin "P$N24") (pinfunction "DEC5_P$N24") (pintype "bidirectional"))
    )
    (net (code "47") (name "Net-(U1-P0.00{slash}XL1)") (class "Default")
      (node (ref "C17") (pin "2") (pinfunction "2_2") (pintype "passive"))
      (node (ref "U1") (pin "P$D2") (pinfunction "P0.00/XL1_P$D2") (pintype "bidirectional"))
      (node (ref "X2") (pin "2") (pinfunction "2_2") (pintype "passive"))
    )
    (net (code "48") (name "Net-(U1-P0.01{slash}XL2)") (class "Default")
      (node (ref "C18\\") (pin "2") (pinfunction "2_2") (pintype "passive"))
      (node (ref "U1") (pin "P$F2") (pinfunction "P0.01/XL2_P$F2") (pintype "bidirectional"))
      (node (ref "X2") (pin "1") (pinfunction "1_1") (pintype "passive"))
    )
    (net (code "49") (name "Net-(U1-XC1)") (class "Default")
      (node (ref "C1") (pin "1") (pinfunction "1_1") (pintype "passive"))
      (node (ref "U1") (pin "P$B24") (pinfunction "XC1_P$B24") (pintype "input"))
      (node (ref "X1") (pin "1") (pinfunction "1_1") (pintype "passive"))
    )
    (net (code "50") (name "Net-(U1-XC2)") (class "Default")
      (node (ref "C2") (pin "2") (pinfunction "2_2") (pintype "passive"))
      (node (ref "U1") (pin "P$A23") (pinfunction "XC2_P$A23") (pintype "output"))
      (node (ref "X1") (pin "3") (pinfunction "3_3") (pintype "passive"))
    )
    (net (code "51") (name "OUT+") (class "Default")
      (node (ref "IC2") (pin "A3") (pinfunction "OUT+_A3") (pintype "bidirectional"))
      (node (ref "TP_OP") (pin "TP") (pinfunction "TP_TP") (pintype "input"))
    )
    (net (code "52") (name "OUT-") (class "Default")
      (node (ref "IC2") (pin "C3") (pinfunction "OUT-_C3") (pintype "bidirectional"))
      (node (ref "TP_ON") (pin "TP") (pinfunction "TP_TP") (pintype "input"))
    )
    (net (code "53") (name "P0.04") (class "Default")
      (node (ref "U1") (pin "P$J1") (pinfunction "P0.04/AIN2_P$J1") (pintype "bidirectional"))
    )
    (net (code "54") (name "P0.09") (class "Default")
      (node (ref "U1") (pin "P$L24") (pinfunction "P0.09/NFC1_P$L24") (pintype "bidirectional"))
    )
    (net (code "55") (name "P0.13") (class "Default")
      (node (ref "C30") (pin "2") (pinfunction "2_2") (pintype "passive"))
      (node (ref "R5") (pin "2") (pinfunction "2_2") (pintype "bidirectional"))
      (node (ref "SW_UP") (pin "2") (pinfunction "2_2") (pintype "passive"))
      (node (ref "U1") (pin "P$AD8") (pinfunction "P0.13_P$AD8") (pintype "bidirectional"))
    )
    (net (code "56") (name "P0.14") (class "Default")
      (node (ref "C31") (pin "2") (pinfunction "2_2") (pintype "passive"))
      (node (ref "R8") (pin "2") (pinfunction "2_2") (pintype "bidirectional"))
      (node (ref "SW_ENT") (pin "2") (pinfunction "2_2") (pintype "passive"))
      (node (ref "U1") (pin "P$AC9") (pinfunction "P0.14_P$AC9") (pintype "bidirectional"))
    )
    (net (code "57") (name "P0.19") (class "Default")
      (node (ref "U1") (pin "P$AC15") (pinfunction "P0.19_P$AC15") (pintype "bidirectional"))
    )
    (net (code "58") (name "P0.20") (class "Default")
      (node (ref "U1") (pin "P$AD16") (pinfunction "P0.20_P$AD16") (pintype "bidirectional"))
    )
    (net (code "59") (name "P0.21") (class "Default")
      (node (ref "U1") (pin "P$AC17") (pinfunction "P0.21_P$AC17") (pintype "bidirectional"))
    )
    (net (code "60") (name "P0.22") (class "Default")
      (node (ref "U1") (pin "P$AD18") (pinfunction "P0.22_P$AD18") (pintype "bidirectional"))
    )
    (net (code "61") (name "P0.23") (class "Default")
      (node (ref "U1") (pin "P$AC19") (pinfunction "P0.23_P$AC19") (pintype "bidirectional"))
    )
    (net (code "62") (name "P0.24") (class "Default")
      (node (ref "U1") (pin "P$AD20") (pinfunction "P0.24_P$AD20") (pintype "bidirectional"))
    )
    (net (code "63") (name "P0.25") (class "Default")
      (node (ref "U1") (pin "P$AC21") (pinfunction "P0.25_P$AC21") (pintype "bidirectional"))
    )
    (net (code "64") (name "P0.26") (class "Default")
      (node (ref "U1") (pin "P$G1") (pinfunction "P0.26_P$G1") (pintype "bidirectional"))
    )
    (net (code "65") (name "P0.27") (class "Default")
      (node (ref "U1") (pin "P$H2") (pinfunction "P0.27_P$H2") (pintype "bidirectional"))
    )
    (net (code "66") (name "P0.28") (class "Default")
      (node (ref "U1") (pin "P$B11") (pinfunction "P0.28/AIN4_P$B11") (pintype "bidirectional"))
    )
    (net (code "67") (name "P0.29") (class "Default")
      (node (ref "U1") (pin "P$A10") (pinfunction "P0.29/AIN5_P$A10") (pintype "bidirectional"))
    )
    (net (code "68") (name "P0.30") (class "Default")
      (node (ref "U1") (pin "P$B9") (pinfunction "P0.30/AIN6_P$B9") (pintype "bidirectional"))
    )
    (net (code "69") (name "P0.31") (class "Default")
      (node (ref "U1") (pin "P$A8") (pinfunction "P0.31/AIN7_P$A8") (pintype "bidirectional"))
    )
    (net (code "70") (name "P1.01") (class "Default")
      (node (ref "Q1") (pin "1") (pinfunction "G_1") (pintype "bidirectional"))
      (node (ref "R_PWR_EPD") (pin "2") (pinfunction "2_2") (pintype "bidirectional"))
      (node (ref "U1") (pin "P$Y23") (pinfunction "P1.01_P$Y23") (pintype "bidirectional"))
    )
    (net (code "71") (name "P1.02") (class "Default")
      (node (ref "C29") (pin "2") (pinfunction "2_2") (pintype "passive"))
      (node (ref "R7") (pin "2") (pinfunction "2_2") (pintype "bidirectional"))
      (node (ref "SW_DN") (pin "2") (pinfunction "2_2") (pintype "passive"))
      (node (ref "U1") (pin "P$W24") (pinfunction "P1.02_P$W24") (pintype "bidirectional"))
    )
    (net (code "72") (name "P1.03") (class "Default")
      (node (ref "U1") (pin "P$V23") (pinfunction "P1.03_P$V23") (pintype "bidirectional"))
    )
    (net (code "73") (name "P1.04") (class "Default")
      (node (ref "U1") (pin "P$U24") (pinfunction "P1.04_P$U24") (pintype "bidirectional"))
    )
    (net (code "74") (name "P1.05") (class "Default")
      (node (ref "U1") (pin "P$T23") (pinfunction "P1.05_P$T23") (pintype "bidirectional"))
    )
    (net (code "75") (name "P1.06") (class "Default")
      (node (ref "U1") (pin "P$R24") (pinfunction "P1.06_P$R24") (pintype "bidirectional"))
    )
    (net (code "76") (name "P1.07") (class "Default")
      (node (ref "U1") (pin "P$P23") (pinfunction "P1.07_P$P23") (pintype "bidirectional"))
    )
    (net (code "77") (name "P1.09") (class "Default")
      (node (ref "U1") (pin "P$R1") (pinfunction "P1.09_P$R1") (pintype "bidirectional"))
    )
    (net (code "78") (name "P1.10") (class "Default")
      (node (ref "U1") (pin "P$A20") (pinfunction "P1.10_P$A20") (pintype "bidirectional"))
    )
    (net (code "79") (name "P1.11") (class "Default")
      (node (ref "U1") (pin "P$B19") (pinfunction "P1.11_P$B19") (pintype "bidirectional"))
    )
    (net (code "80") (name "P1.12") (class "Default")
      (node (ref "U1") (pin "P$B17") (pinfunction "P1.12_P$B17") (pintype "bidirectional"))
    )
    (net (code "81") (name "P1.13") (class "Default")
      (node (ref "U1") (pin "P$A16") (pinfunction "P1.13_P$A16") (pintype "bidirectional"))
    )
    (net (code "82") (name "P1.14") (class "Default")
      (node (ref "U1") (pin "P$B15") (pinfunction "P1.14_P$B15") (pintype "bidirectional"))
    )
    (net (code "83") (name "P1.15") (class "Default")
      (node (ref "U1") (pin "P$A14") (pinfunction "P1.15_P$A14") (pintype "bidirectional"))
    )
    (net (code "84") (name "PMIC_INT") (class "Default")
      (node (ref "IC1") (pin "A1") (pinfunction "~{INT}_A1") (pintype "bidirectional"))
      (node (ref "U1") (pin "P$T2") (pinfunction "P0.11_P$T2") (pintype "bidirectional"))
    )
    (net (code "85") (name "PREVGH") (class "Default")
      (node (ref "D5") (pin "1") (pinfunction "K_1") (pintype "bidirectional"))
      (node (ref "EDP_C9") (pin "2") (pinfunction "2_2") (pintype "passive"))
      (node (ref "J2") (pin "21") (pinfunction "21_21") (pintype "bidirectional"))
    )
    (net (code "86") (name "PREVGL") (class "Default")
      (node (ref "D2") (pin "2") (pinfunction "A_2") (pintype "bidirectional"))
      (node (ref "EDP_C11") (pin "1") (pinfunction "1_1") (pintype "passive"))
      (node (ref "J2") (pin "23") (pinfunction "23_23") (pintype "bidirectional"))
    )
    (net (code "87") (name "RESE") (class "Default")
      (node (ref "J2") (pin "3") (pinfunction "3_3") (pintype "bidirectional"))
      (node (ref "Q3") (pin "2") (pinfunction "S_2") (pintype "bidirectional"))
      (node (ref "R1_EP_DR1") (pin "1") (pinfunction "1_1") (pintype "bidirectional"))
    )
    (net (code "88") (name "RESET") (class "Default")
      (node (ref "J1") (pin "6") (pinfunction "6_6") (pintype "bidirectional"))
      (node (ref "TP_RESET") (pin "TP") (pinfunction "TP_TP") (pintype "input"))
      (node (ref "U1") (pin "P$AC13") (pinfunction "P0.18/RESET_P$AC13") (pintype "bidirectional"))
    )
    (net (code "89") (name "SCK") (class "Default")
      (node (ref "J2") (pin "13") (pinfunction "13_13") (pintype "bidirectional"))
      (node (ref "U1") (pin "P$A12") (pinfunction "P0.02/AIN0_P$A12") (pintype "bidirectional"))
    )
    (net (code "90") (name "SCL") (class "Default")
      (node (ref "IC1") (pin "B1") (pinfunction "SCL_B1") (pintype "bidirectional"))
      (node (ref "IC2") (pin "C1") (pinfunction "SCL_C1") (pintype "bidirectional"))
      (node (ref "IC3") (pin "12") (pinfunction "SCX_12") (pintype "bidirectional"))
      (node (ref "R1") (pin "1") (pinfunction "1_1") (pintype "bidirectional"))
      (node (ref "R17") (pin "1") (pinfunction "1_1") (pintype "bidirectional"))
      (node (ref "TP_SCL") (pin "TP") (pinfunction "TP_TP") (pintype "input"))
      (node (ref "U1") (pin "P$M2") (pinfunction "P0.07_P$M2") (pintype "bidirectional"))
      (node (ref "U2") (pin "7") (pinfunction "SCL_7") (pintype "input"))
    )
    (net (code "91") (name "SDA") (class "Default")
      (node (ref "IC1") (pin "C1") (pinfunction "SDA_C1") (pintype "bidirectional"))
      (node (ref "IC2") (pin "B2") (pinfunction "SDA_B2") (pintype "bidirectional"))
      (node (ref "IC3") (pin "2") (pinfunction "SDX_2") (pintype "bidirectional"))
      (node (ref "R18") (pin "1") (pinfunction "1_1") (pintype "bidirectional"))
      (node (ref "R2") (pin "1") (pinfunction "1_1") (pintype "bidirectional"))
      (node (ref "TP_SDA") (pin "TP") (pinfunction "TP_TP") (pintype "input"))
      (node (ref "U1") (pin "P$L1") (pinfunction "P0.06_P$L1") (pintype "bidirectional"))
      (node (ref "U2") (pin "8") (pinfunction "SDA_8") (pintype "bidirectional"))
    )
    (net (code "92") (name "SWDCLK") (class "Default")
      (node (ref "J1") (pin "4") (pinfunction "4_4") (pintype "bidirectional"))
      (node (ref "TP_SWDCLK") (pin "TP") (pinfunction "TP_TP") (pintype "input"))
      (node (ref "U1") (pin "P$AA24") (pinfunction "SWDCLK_P$AA24") (pintype "input"))
    )
    (net (code "93") (name "SWDIO") (class "Default")
      (node (ref "J1") (pin "2") (pinfunction "2_2") (pintype "bidirectional"))
      (node (ref "TP_SWDIO") (pin "TP") (pinfunction "TP_TP") (pintype "input"))
      (node (ref "U1") (pin "P$AC24") (pinfunction "SWDIO_P$AC24") (pintype "bidirectional"))
    )
    (net (code "94") (name "SWO") (class "Default")
      (node (ref "TP_SWO") (pin "TP") (pinfunction "TP_TP") (pintype "input"))
      (node (ref "U1") (pin "P$AD22") (pinfunction "P1.00_P$AD22") (pintype "bidirectional"))
    )
    (net (code "95") (name "VBAT") (class "Default")
      (node (ref "C27") (pin "2") (pinfunction "2_2") (pintype "passive"))
      (node (ref "C37") (pin "2") (pinfunction "2_2") (pintype "passive"))
      (node (ref "IC1") (pin "C2") (pinfunction "BAT_C2") (pintype "bidirectional"))
      (node (ref "TP_VBAT") (pin "TP") (pinfunction "TP_TP") (pintype "input"))
      (node (ref "U2") (pin "2") (pinfunction "CELL_2") (pintype "power_in"))
      (node (ref "U2") (pin "3") (pinfunction "VDD_3") (pintype "power_in"))
    )
    (net (code "96") (name "VBUS") (class "Default")
      (node (ref "C21") (pin "1") (pinfunction "1_1") (pintype "passive"))
      (node (ref "C38") (pin "2") (pinfunction "2_2") (pintype "passive"))
      (node (ref "C42") (pin "2") (pinfunction "2_2") (pintype "passive"))
      (node (ref "C43") (pin "1") (pinfunction "1_1") (pintype "passive"))
      (node (ref "D3") (pin "5") (pinfunction "VBUS_5") (pintype "bidirectional"))
      (node (ref "IC1") (pin "A2") (pinfunction "IN_A2") (pintype "bidirectional"))
      (node (ref "J4") (pin "A4_B9") (pinfunction "VBUS_A4_B9") (pintype "power_in"))
      (node (ref "J4") (pin "A9_B4") (pinfunction "VBUS_A9_B4") (pintype "power_in"))
      (node (ref "U1") (pin "P$AD2") (pinfunction "VBUS_P$AD2") (pintype "power_in"))
    )
    (net (code "97") (name "VREG") (class "Default")
      (node (ref "C23") (pin "1") (pinfunction "1_1") (pintype "passive"))
      (node (ref "C24") (pin "2") (pinfunction "2_2") (pintype "passive"))
      (node (ref "C39") (pin "1") (pinfunction "1_1") (pintype "passive"))
      (node (ref "IC1") (pin "B2") (pinfunction "SYS_B2") (pintype "bidirectional"))
      (node (ref "IC9") (pin "A1") (pinfunction "EN_A1") (pintype "bidirectional"))
      (node (ref "IC9") (pin "A2") (pinfunction "VIN_1_A2") (pintype "bidirectional"))
      (node (ref "IC9") (pin "A3") (pinfunction "VIN_2_A3") (pintype "bidirectional"))
      (node (ref "TP_VREG") (pin "TP") (pinfunction "TP_TP") (pintype "input"))
    )
    (net (code "98") (name "unconnected-(ANT1-NC-Pad2)") (class "Default")
      (node (ref "ANT1") (pin "2") (pinfunction "NC_2") (pintype "no_connect"))
    )
    (net (code "99") (name "unconnected-(IC3-ASCL-Pad11)") (class "Default")
      (node (ref "IC3") (pin "11") (pinfunction "ASCL_11") (pintype "bidirectional"))
    )
    (net (code "100") (name "unconnected-(IC3-ASDA-Pad4)") (class "Default")
      (node (ref "IC3") (pin "4") (pinfunction "ASDA_4") (pintype "bidirectional"))
    )
    (net (code "101") (name "unconnected-(J2-Pad1)") (class "Default")
      (node (ref "J2") (pin "1") (pinfunction "1_1") (pintype "bidirectional"))
    )
    (net (code "102") (name "unconnected-(J2-Pad6)") (class "Default")
      (node (ref "J2") (pin "6") (pinfunction "6_6") (pintype "bidirectional"))
    )
    (net (code "103") (name "unconnected-(J2-Pad7)") (class "Default")
      (node (ref "J2") (pin "7") (pinfunction "7_7") (pintype "bidirectional"))
    )
    (net (code "104") (name "unconnected-(J4-SBU1-PadA8)") (class "Default")
      (node (ref "J4") (pin "A8") (pinfunction "SBU1_A8") (pintype "bidirectional"))
    )
    (net (code "105") (name "unconnected-(J4-SBU2-PadB8)") (class "Default")
      (node (ref "J4") (pin "B8") (pinfunction "SBU2_B8") (pintype "bidirectional"))
    )
    (net (code "106") (name "unconnected-(U1-DCCH-PadP$AB2)") (class "Default")
      (node (ref "U1") (pin "P$AB2") (pinfunction "DCCH_P$AB2") (pintype "bidirectional"))
    )
  )
)
